# mcu.net
KiCad netlist of a schematic drawn in Altium Designer
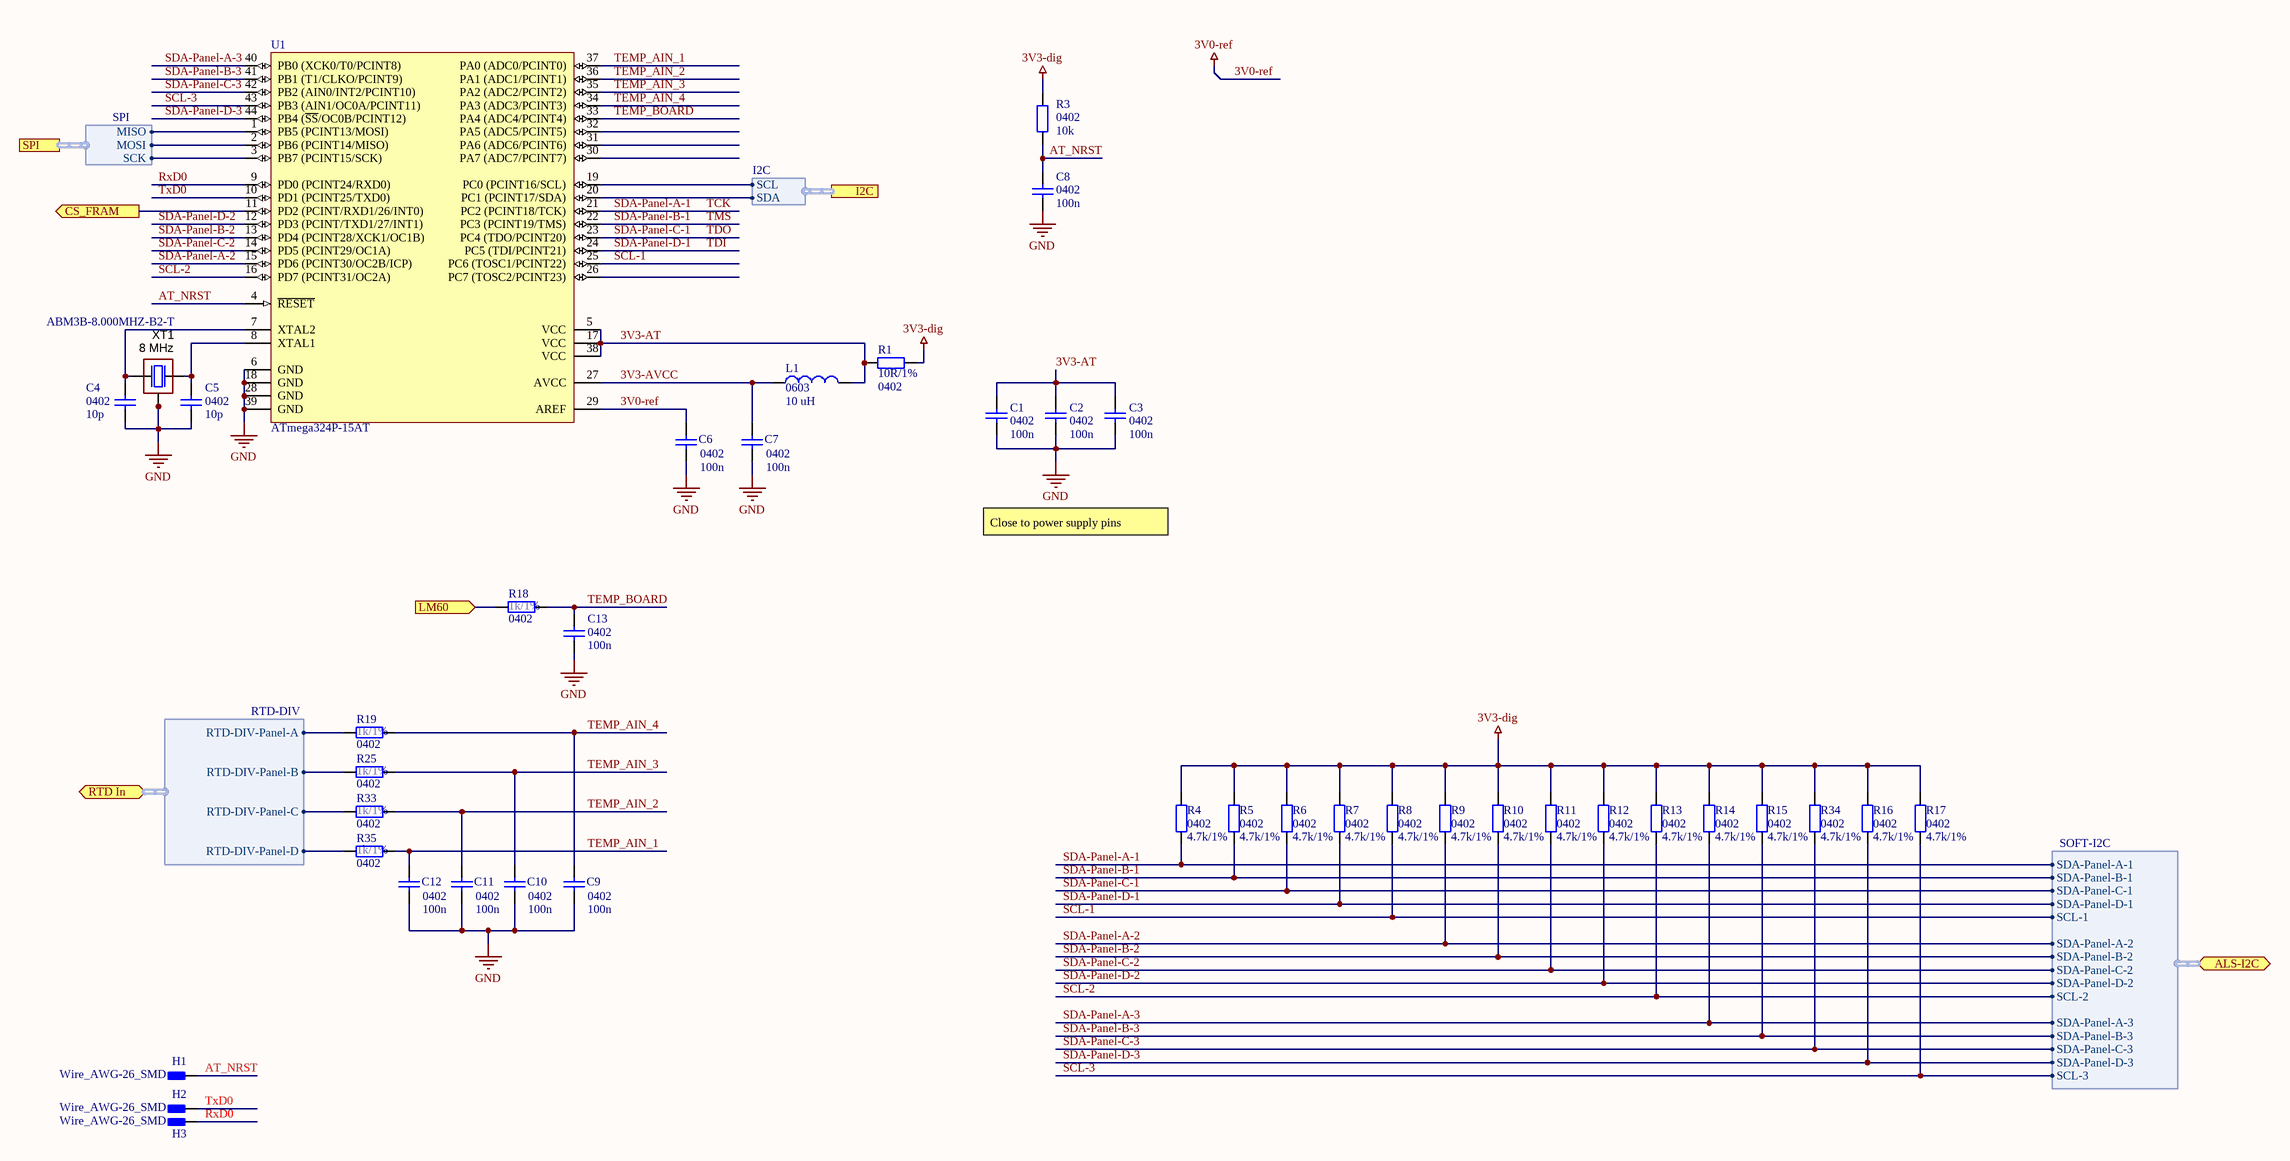
[diagram p0: mcu.SchDoc]

(export (version "E")
  (design (tool "Eeschema 10.0.6"))
  (components
    (comp (ref "C1")
      (value "0402")
      (footprint "SMD_Capacitor_0402")
      (description "Capacitor")
      (fields (field (name "ALTIUM_VALUE") "100n") (field (name "PUBLISHER") "Altium Limited"))
      (libsource (lib "Miscellaneous Devices") (part "Cap"))
    )
    (comp (ref "C2")
      (value "0402")
      (footprint "SMD_Capacitor_0402")
      (description "Capacitor")
      (fields (field (name "ALTIUM_VALUE") "100n") (field (name "PUBLISHER") "Altium Limited"))
      (libsource (lib "Miscellaneous Devices") (part "Cap"))
    )
    (comp (ref "C3")
      (value "0402")
      (footprint "SMD_Capacitor_0402")
      (description "Capacitor")
      (fields (field (name "ALTIUM_VALUE") "100n") (field (name "PUBLISHER") "Altium Limited"))
      (libsource (lib "Miscellaneous Devices") (part "Cap"))
    )
    (comp (ref "C4")
      (value "0402")
      (footprint "SMD_Capacitor_0402")
      (description "Capacitor")
      (fields (field (name "ALTIUM_VALUE") "10p") (field (name "PUBLISHER") "Altium Limited"))
      (libsource (lib "Miscellaneous Devices") (part "Cap"))
    )
    (comp (ref "C5")
      (value "0402")
      (footprint "SMD_Capacitor_0402")
      (description "Capacitor")
      (fields (field (name "ALTIUM_VALUE") "10p") (field (name "PUBLISHER") "Altium Limited"))
      (libsource (lib "Miscellaneous Devices") (part "Cap"))
    )
    (comp (ref "C6")
      (value "0402")
      (footprint "SMD_Capacitor_0402")
      (description "Capacitor")
      (fields (field (name "ALTIUM_VALUE") "100n") (field (name "PUBLISHER") "Altium Limited"))
      (libsource (lib "Miscellaneous Devices") (part "Cap"))
    )
    (comp (ref "C7")
      (value "0402")
      (footprint "SMD_Capacitor_0402")
      (description "Capacitor")
      (fields (field (name "ALTIUM_VALUE") "100n") (field (name "PUBLISHER") "Altium Limited"))
      (libsource (lib "Miscellaneous Devices") (part "Cap"))
    )
    (comp (ref "C8")
      (value "0402")
      (footprint "SMD_Capacitor_0402")
      (description "Capacitor")
      (fields (field (name "ALTIUM_VALUE") "100n") (field (name "PUBLISHER") "Altium Limited"))
      (libsource (lib "Miscellaneous Devices") (part "Cap"))
    )
    (comp (ref "C9")
      (value "0402")
      (footprint "SMD_Capacitor_0402")
      (description "Capacitor")
      (fields (field (name "ALTIUM_VALUE") "100n") (field (name "PUBLISHER") "Altium Limited"))
      (libsource (lib "Miscellaneous Devices") (part "Cap"))
    )
    (comp (ref "C10")
      (value "0402")
      (footprint "SMD_Capacitor_0402")
      (description "Capacitor")
      (fields (field (name "ALTIUM_VALUE") "100n") (field (name "PUBLISHER") "Altium Limited"))
      (libsource (lib "Miscellaneous Devices") (part "Cap"))
    )
    (comp (ref "C11")
      (value "0402")
      (footprint "SMD_Capacitor_0402")
      (description "Capacitor")
      (fields (field (name "ALTIUM_VALUE") "100n") (field (name "PUBLISHER") "Altium Limited"))
      (libsource (lib "Miscellaneous Devices") (part "Cap"))
    )
    (comp (ref "C12")
      (value "0402")
      (footprint "SMD_Capacitor_0402")
      (description "Capacitor")
      (fields (field (name "ALTIUM_VALUE") "100n") (field (name "PUBLISHER") "Altium Limited"))
      (libsource (lib "Miscellaneous Devices") (part "Cap"))
    )
    (comp (ref "C13")
      (value "0402")
      (footprint "SMD_Capacitor_0402")
      (description "Capacitor")
      (fields (field (name "ALTIUM_VALUE") "100n") (field (name "PUBLISHER") "Altium Limited"))
      (libsource (lib "Miscellaneous Devices") (part "Cap"))
    )
    (comp (ref "H1")
      (value "Wire_AWG-26_SMD")
      (footprint "Wire_AWG-26_SMD")
      (description "SMD wire solder point.")
      (libsource (lib "connectors_printed-circuit-board") (part "Wire_AWG-26_SMD"))
    )
    (comp (ref "H2")
      (value "Wire_AWG-26_SMD")
      (footprint "Wire_AWG-26_SMD")
      (description "SMD wire solder point.")
      (libsource (lib "connectors_printed-circuit-board") (part "Wire_AWG-26_SMD"))
    )
    (comp (ref "H3")
      (value "Wire_AWG-26_SMD")
      (footprint "Wire_AWG-26_SMD")
      (description "SMD wire solder point.")
      (libsource (lib "connectors_printed-circuit-board") (part "Wire_AWG-26_SMD"))
    )
    (comp (ref "L1")
      (value "10 uH")
      (footprint "SMD_Resistor_0603")
      (description "Inductor")
      (fields (field (name "PACKAGEREFERENCE") "0603") (field (name "PUBLISHER") "Altium Limited"))
      (libsource (lib "Miscellaneous Devices") (part "Inductor"))
    )
    (comp (ref "R1")
      (value "10R/1%")
      (footprint "SMD_Resistor_0402")
      (description "10R/1% Vishay CRCW 0402 Resistor. 63mW, 100ppm, 50V.")
      (fields
        (field (name "MANUFACTURER") "Vishay")
        (field (name "MANUFACTURERPARTNUMBER") "CRCW040210R0FKxxxx")
        (field (name "PACKAGE") "0402")
      )
      (libsource (lib "resistors") (part "CRCW040210R0FKxxxx"))
    )
    (comp (ref "R3")
      (value "0402")
      (footprint "SMD_Capacitor_0402")
      (description "Resistor")
      (fields (field (name "ALTIUM_VALUE") "10k") (field (name "PUBLISHER") "Altium Limited"))
      (libsource (lib "Miscellaneous Devices") (part "Res2"))
    )
    (comp (ref "R4")
      (value "4.7k/1%")
      (footprint "SMD_Resistor_0402")
      (description "4.7k/1% Vishay CRCW 0402 Resistor. 63mW, 100ppm, 50V.")
      (fields
        (field (name "MANUFACTURERPARTNUMBER") "CRCW04024K70FKxxxx")
        (field (name "MANUFACTURER") "Vishay")
        (field (name "PACKAGE") "0402")
      )
      (libsource (lib "resistors") (part "CRCW04024K70FKxxxx"))
    )
    (comp (ref "R5")
      (value "4.7k/1%")
      (footprint "SMD_Resistor_0402")
      (description "4.7k/1% Vishay CRCW 0402 Resistor. 63mW, 100ppm, 50V.")
      (fields
        (field (name "MANUFACTURERPARTNUMBER") "CRCW04024K70FKxxxx")
        (field (name "MANUFACTURER") "Vishay")
        (field (name "PACKAGE") "0402")
      )
      (libsource (lib "resistors") (part "CRCW04024K70FKxxxx"))
    )
    (comp (ref "R6")
      (value "4.7k/1%")
      (footprint "SMD_Resistor_0402")
      (description "4.7k/1% Vishay CRCW 0402 Resistor. 63mW, 100ppm, 50V.")
      (fields
        (field (name "MANUFACTURERPARTNUMBER") "CRCW04024K70FKxxxx")
        (field (name "MANUFACTURER") "Vishay")
        (field (name "PACKAGE") "0402")
      )
      (libsource (lib "resistors") (part "CRCW04024K70FKxxxx"))
    )
    (comp (ref "R7")
      (value "4.7k/1%")
      (footprint "SMD_Resistor_0402")
      (description "4.7k/1% Vishay CRCW 0402 Resistor. 63mW, 100ppm, 50V.")
      (fields
        (field (name "MANUFACTURERPARTNUMBER") "CRCW04024K70FKxxxx")
        (field (name "MANUFACTURER") "Vishay")
        (field (name "PACKAGE") "0402")
      )
      (libsource (lib "resistors") (part "CRCW04024K70FKxxxx"))
    )
    (comp (ref "R8")
      (value "4.7k/1%")
      (footprint "SMD_Resistor_0402")
      (description "4.7k/1% Vishay CRCW 0402 Resistor. 63mW, 100ppm, 50V.")
      (fields
        (field (name "MANUFACTURERPARTNUMBER") "CRCW04024K70FKxxxx")
        (field (name "MANUFACTURER") "Vishay")
        (field (name "PACKAGE") "0402")
      )
      (libsource (lib "resistors") (part "CRCW04024K70FKxxxx"))
    )
    (comp (ref "R9")
      (value "4.7k/1%")
      (footprint "SMD_Resistor_0402")
      (description "4.7k/1% Vishay CRCW 0402 Resistor. 63mW, 100ppm, 50V.")
      (fields
        (field (name "MANUFACTURERPARTNUMBER") "CRCW04024K70FKxxxx")
        (field (name "MANUFACTURER") "Vishay")
        (field (name "PACKAGE") "0402")
      )
      (libsource (lib "resistors") (part "CRCW04024K70FKxxxx"))
    )
    (comp (ref "R10")
      (value "4.7k/1%")
      (footprint "SMD_Resistor_0402")
      (description "4.7k/1% Vishay CRCW 0402 Resistor. 63mW, 100ppm, 50V.")
      (fields
        (field (name "MANUFACTURERPARTNUMBER") "CRCW04024K70FKxxxx")
        (field (name "MANUFACTURER") "Vishay")
        (field (name "PACKAGE") "0402")
      )
      (libsource (lib "resistors") (part "CRCW04024K70FKxxxx"))
    )
    (comp (ref "R11")
      (value "4.7k/1%")
      (footprint "SMD_Resistor_0402")
      (description "4.7k/1% Vishay CRCW 0402 Resistor. 63mW, 100ppm, 50V.")
      (fields
        (field (name "MANUFACTURERPARTNUMBER") "CRCW04024K70FKxxxx")
        (field (name "MANUFACTURER") "Vishay")
        (field (name "PACKAGE") "0402")
      )
      (libsource (lib "resistors") (part "CRCW04024K70FKxxxx"))
    )
    (comp (ref "R12")
      (value "4.7k/1%")
      (footprint "SMD_Resistor_0402")
      (description "4.7k/1% Vishay CRCW 0402 Resistor. 63mW, 100ppm, 50V.")
      (fields
        (field (name "MANUFACTURERPARTNUMBER") "CRCW04024K70FKxxxx")
        (field (name "MANUFACTURER") "Vishay")
        (field (name "PACKAGE") "0402")
      )
      (libsource (lib "resistors") (part "CRCW04024K70FKxxxx"))
    )
    (comp (ref "R13")
      (value "4.7k/1%")
      (footprint "SMD_Resistor_0402")
      (description "4.7k/1% Vishay CRCW 0402 Resistor. 63mW, 100ppm, 50V.")
      (fields
        (field (name "MANUFACTURERPARTNUMBER") "CRCW04024K70FKxxxx")
        (field (name "MANUFACTURER") "Vishay")
        (field (name "PACKAGE") "0402")
      )
      (libsource (lib "resistors") (part "CRCW04024K70FKxxxx"))
    )
    (comp (ref "R14")
      (value "4.7k/1%")
      (footprint "SMD_Resistor_0402")
      (description "4.7k/1% Vishay CRCW 0402 Resistor. 63mW, 100ppm, 50V.")
      (fields
        (field (name "MANUFACTURERPARTNUMBER") "CRCW04024K70FKxxxx")
        (field (name "MANUFACTURER") "Vishay")
        (field (name "PACKAGE") "0402")
      )
      (libsource (lib "resistors") (part "CRCW04024K70FKxxxx"))
    )
    (comp (ref "R15")
      (value "4.7k/1%")
      (footprint "SMD_Resistor_0402")
      (description "4.7k/1% Vishay CRCW 0402 Resistor. 63mW, 100ppm, 50V.")
      (fields
        (field (name "MANUFACTURERPARTNUMBER") "CRCW04024K70FKxxxx")
        (field (name "MANUFACTURER") "Vishay")
        (field (name "PACKAGE") "0402")
      )
      (libsource (lib "resistors") (part "CRCW04024K70FKxxxx"))
    )
    (comp (ref "R16")
      (value "4.7k/1%")
      (footprint "SMD_Resistor_0402")
      (description "4.7k/1% Vishay CRCW 0402 Resistor. 63mW, 100ppm, 50V.")
      (fields
        (field (name "MANUFACTURERPARTNUMBER") "CRCW04024K70FKxxxx")
        (field (name "MANUFACTURER") "Vishay")
        (field (name "PACKAGE") "0402")
      )
      (libsource (lib "resistors") (part "CRCW04024K70FKxxxx"))
    )
    (comp (ref "R17")
      (value "4.7k/1%")
      (footprint "SMD_Resistor_0402")
      (description "4.7k/1% Vishay CRCW 0402 Resistor. 63mW, 100ppm, 50V.")
      (fields
        (field (name "MANUFACTURERPARTNUMBER") "CRCW04024K70FKxxxx")
        (field (name "MANUFACTURER") "Vishay")
        (field (name "PACKAGE") "0402")
      )
      (libsource (lib "resistors") (part "CRCW04024K70FKxxxx"))
    )
    (comp (ref "R18")
      (value "1k/1%")
      (footprint "SMD_Resistor_0402")
      (description "1k/1% Vishay CRCW 0402 Resistor. 63mW, 100ppm, 50V.")
      (fields
        (field (name "MANUFACTURER") "Vishay")
        (field (name "MANUFACTURERPARTNUMBER") "CRCW04021K00FKxxxx")
        (field (name "PACKAGE") "0402")
      )
      (libsource (lib "resistors") (part "CRCW04021K00FKxxxx"))
    )
    (comp (ref "R19")
      (value "1k/1%")
      (footprint "SMD_Resistor_0402")
      (description "1k/1% Vishay CRCW 0402 Resistor. 63mW, 100ppm, 50V.")
      (fields
        (field (name "MANUFACTURER") "Vishay")
        (field (name "MANUFACTURERPARTNUMBER") "CRCW04021K00FKxxxx")
        (field (name "PACKAGE") "0402")
      )
      (libsource (lib "resistors") (part "CRCW04021K00FKxxxx"))
    )
    (comp (ref "R25")
      (value "1k/1%")
      (footprint "SMD_Resistor_0402")
      (description "1k/1% Vishay CRCW 0402 Resistor. 63mW, 100ppm, 50V.")
      (fields
        (field (name "MANUFACTURER") "Vishay")
        (field (name "MANUFACTURERPARTNUMBER") "CRCW04021K00FKxxxx")
        (field (name "PACKAGE") "0402")
      )
      (libsource (lib "resistors") (part "CRCW04021K00FKxxxx"))
    )
    (comp (ref "R33")
      (value "1k/1%")
      (footprint "SMD_Resistor_0402")
      (description "1k/1% Vishay CRCW 0402 Resistor. 63mW, 100ppm, 50V.")
      (fields
        (field (name "MANUFACTURER") "Vishay")
        (field (name "MANUFACTURERPARTNUMBER") "CRCW04021K00FKxxxx")
        (field (name "PACKAGE") "0402")
      )
      (libsource (lib "resistors") (part "CRCW04021K00FKxxxx"))
    )
    (comp (ref "R34")
      (value "4.7k/1%")
      (footprint "SMD_Resistor_0402")
      (description "4.7k/1% Vishay CRCW 0402 Resistor. 63mW, 100ppm, 50V.")
      (fields
        (field (name "MANUFACTURERPARTNUMBER") "CRCW04024K70FKxxxx")
        (field (name "MANUFACTURER") "Vishay")
        (field (name "PACKAGE") "0402")
      )
      (libsource (lib "resistors") (part "CRCW04024K70FKxxxx"))
    )
    (comp (ref "R35")
      (value "1k/1%")
      (footprint "SMD_Resistor_0402")
      (description "1k/1% Vishay CRCW 0402 Resistor. 63mW, 100ppm, 50V.")
      (fields
        (field (name "MANUFACTURER") "Vishay")
        (field (name "MANUFACTURERPARTNUMBER") "CRCW04021K00FKxxxx")
        (field (name "PACKAGE") "0402")
      )
      (libsource (lib "resistors") (part "CRCW04021K00FKxxxx"))
    )
    (comp (ref "U1")
      (value "ATmega324P-15AT")
      (footprint "44ML_N")
      (libsource (lib "Atmel Microcontroller AVR Automotive") (part "ATmega324P-15AT"))
    )
    (comp (ref "XT1")
      (value "8 MHz")
      (footprint "SMD, 5mm x 3.2mm")
      (description "Resonator Ceramic")
      (fields (field (name "MANUFACTURER PART NUMBER") "ABM3B-8.000MHZ-B2-T"))
      (libsource (lib "crystal") (part "ABM3B-8.000MHZ-B2-T"))
    )
  )
  (nets
    (net (code "5") (name "/3V3-AT") (class "Default")
      (node (ref "C1") (pin "2") (pinfunction "2_2") (pintype "passive"))
      (node (ref "C2") (pin "2") (pinfunction "2_2") (pintype "passive"))
      (node (ref "C3") (pin "2") (pinfunction "2_2") (pintype "passive"))
      (node (ref "L1") (pin "2") (pinfunction "2_2") (pintype "passive"))
      (node (ref "R1") (pin "2") (pinfunction "2_2") (pintype "passive"))
      (node (ref "U1") (pin "17") (pinfunction "VCC_17") (pintype "power_in"))
      (node (ref "U1") (pin "38") (pinfunction "VCC_38") (pintype "power_in"))
      (node (ref "U1") (pin "5") (pinfunction "VCC_5") (pintype "power_in"))
    )
    (net (code "6") (name "/3V3-AVCC") (class "Default")
      (node (ref "C7") (pin "2") (pinfunction "2_2") (pintype "passive"))
      (node (ref "L1") (pin "1") (pinfunction "1_1") (pintype "passive"))
      (node (ref "U1") (pin "27") (pinfunction "AVCC_27") (pintype "power_in"))
    )
    (net (code "7") (name "/AT_NRST") (class "Default")
      (node (ref "C8") (pin "2") (pinfunction "2_2") (pintype "passive"))
      (node (ref "H1") (pin "1") (pinfunction "1_1") (pintype "passive"))
      (node (ref "R3") (pin "1") (pinfunction "1_1") (pintype "passive"))
      (node (ref "U1") (pin "4") (pinfunction "~{RESET}_4") (pintype "input"))
    )
    (net (code "8") (name "/CS_FRAM") (class "Default")
      (node (ref "U1") (pin "11") (pinfunction "PD2_(PCINT/RXD1/26/INT0)_11") (pintype "bidirectional"))
    )
    (net (code "9") (name "/LM60") (class "Default")
      (node (ref "R18") (pin "1") (pinfunction "1_1") (pintype "passive"))
    )
    (net (code "10") (name "/MISO") (class "Default")
      (node (ref "U1") (pin "1") (pinfunction "PB5_(PCINT13/MOSI)_1") (pintype "bidirectional"))
    )
    (net (code "11") (name "/MOSI") (class "Default")
      (node (ref "U1") (pin "2") (pinfunction "PB6_(PCINT14/MISO)_2") (pintype "bidirectional"))
    )
    (net (code "12") (name "/RTD-DIV-Panel-A") (class "Default")
      (node (ref "R19") (pin "1") (pinfunction "1_1") (pintype "passive"))
    )
    (net (code "13") (name "/RTD-DIV-Panel-B") (class "Default")
      (node (ref "R25") (pin "1") (pinfunction "1_1") (pintype "passive"))
    )
    (net (code "14") (name "/RTD-DIV-Panel-C") (class "Default")
      (node (ref "R33") (pin "1") (pinfunction "1_1") (pintype "passive"))
    )
    (net (code "15") (name "/RTD-DIV-Panel-D") (class "Default")
      (node (ref "R35") (pin "1") (pinfunction "1_1") (pintype "passive"))
    )
    (net (code "16") (name "/RxD0") (class "Default")
      (node (ref "H3") (pin "1") (pinfunction "1_1") (pintype "passive"))
      (node (ref "U1") (pin "9") (pinfunction "PD0_(PCINT24/RXD0)_9") (pintype "bidirectional"))
    )
    (net (code "17") (name "/SCK") (class "Default")
      (node (ref "U1") (pin "3") (pinfunction "PB7_(PCINT15/SCK)_3") (pintype "bidirectional"))
    )
    (net (code "18") (name "/SCL") (class "Default")
      (node (ref "U1") (pin "19") (pinfunction "PC0_(PCINT16/SCL)_19") (pintype "bidirectional"))
    )
    (net (code "19") (name "/SCL-1") (class "Default")
      (node (ref "R8") (pin "2") (pinfunction "2_2") (pintype "passive"))
      (node (ref "U1") (pin "25") (pinfunction "PC6_(TOSC1/PCINT22)_25") (pintype "bidirectional"))
    )
    (net (code "20") (name "/SCL-2") (class "Default")
      (node (ref "R13") (pin "2") (pinfunction "2_2") (pintype "passive"))
      (node (ref "U1") (pin "16") (pinfunction "PD7_(PCINT31/OC2A)_16") (pintype "bidirectional"))
    )
    (net (code "21") (name "/SCL-3") (class "Default")
      (node (ref "R17") (pin "2") (pinfunction "2_2") (pintype "passive"))
      (node (ref "U1") (pin "43") (pinfunction "PB3_(AIN1/OC0A/PCINT11)_43") (pintype "bidirectional"))
    )
    (net (code "22") (name "/SDA") (class "Default")
      (node (ref "U1") (pin "20") (pinfunction "PC1_(PCINT17/SDA)_20") (pintype "bidirectional"))
    )
    (net (code "23") (name "/SDA-Panel-A-1") (class "Default")
      (node (ref "R4") (pin "2") (pinfunction "2_2") (pintype "passive"))
      (node (ref "U1") (pin "21") (pinfunction "PC2_(PCINT18/TCK)_21") (pintype "bidirectional"))
    )
    (net (code "24") (name "/SDA-Panel-A-2") (class "Default")
      (node (ref "R9") (pin "2") (pinfunction "2_2") (pintype "passive"))
      (node (ref "U1") (pin "15") (pinfunction "PD6_(PCINT30/OC2B/ICP)_15") (pintype "bidirectional"))
    )
    (net (code "25") (name "/SDA-Panel-A-3") (class "Default")
      (node (ref "R14") (pin "2") (pinfunction "2_2") (pintype "passive"))
      (node (ref "U1") (pin "40") (pinfunction "PB0_(XCK0/T0/PCINT8)_40") (pintype "bidirectional"))
    )
    (net (code "26") (name "/SDA-Panel-B-1") (class "Default")
      (node (ref "R5") (pin "2") (pinfunction "2_2") (pintype "passive"))
      (node (ref "U1") (pin "22") (pinfunction "PC3_(PCINT19/TMS)_22") (pintype "bidirectional"))
    )
    (net (code "27") (name "/SDA-Panel-B-2") (class "Default")
      (node (ref "R10") (pin "2") (pinfunction "2_2") (pintype "passive"))
      (node (ref "U1") (pin "13") (pinfunction "PD4_(PCINT28/XCK1/OC1B)_13") (pintype "bidirectional"))
    )
    (net (code "28") (name "/SDA-Panel-B-3") (class "Default")
      (node (ref "R15") (pin "2") (pinfunction "2_2") (pintype "passive"))
      (node (ref "U1") (pin "41") (pinfunction "PB1_(T1/CLKO/PCINT9)_41") (pintype "bidirectional"))
    )
    (net (code "29") (name "/SDA-Panel-C-1") (class "Default")
      (node (ref "R6") (pin "2") (pinfunction "2_2") (pintype "passive"))
      (node (ref "U1") (pin "23") (pinfunction "PC4_(TDO/PCINT20)_23") (pintype "bidirectional"))
    )
    (net (code "30") (name "/SDA-Panel-C-2") (class "Default")
      (node (ref "R11") (pin "2") (pinfunction "2_2") (pintype "passive"))
      (node (ref "U1") (pin "14") (pinfunction "PD5_(PCINT29/OC1A)_14") (pintype "bidirectional"))
    )
    (net (code "31") (name "/SDA-Panel-C-3") (class "Default")
      (node (ref "R34") (pin "2") (pinfunction "2_2") (pintype "passive"))
      (node (ref "U1") (pin "42") (pinfunction "PB2_(AIN0/INT2/PCINT10)_42") (pintype "bidirectional"))
    )
    (net (code "32") (name "/SDA-Panel-D-1") (class "Default")
      (node (ref "R7") (pin "2") (pinfunction "2_2") (pintype "passive"))
      (node (ref "U1") (pin "24") (pinfunction "PC5_(TDI/PCINT21)_24") (pintype "bidirectional"))
    )
    (net (code "33") (name "/SDA-Panel-D-2") (class "Default")
      (node (ref "R12") (pin "2") (pinfunction "2_2") (pintype "passive"))
      (node (ref "U1") (pin "12") (pinfunction "PD3_(PCINT/TXD1/27/INT1)_12") (pintype "bidirectional"))
    )
    (net (code "34") (name "/SDA-Panel-D-3") (class "Default")
      (node (ref "R16") (pin "2") (pinfunction "2_2") (pintype "passive"))
      (node (ref "U1") (pin "44") (pinfunction "PB4_(~{SS}/OC0B/PCINT12)_44") (pintype "bidirectional"))
    )
    (net (code "35") (name "/TEMP_AIN_1") (class "Default")
      (node (ref "C12") (pin "2") (pinfunction "2_2") (pintype "passive"))
      (node (ref "R35") (pin "2") (pinfunction "2_2") (pintype "passive"))
      (node (ref "U1") (pin "37") (pinfunction "PA0_(ADC0/PCINT0)_37") (pintype "bidirectional"))
    )
    (net (code "36") (name "/TEMP_AIN_2") (class "Default")
      (node (ref "C11") (pin "2") (pinfunction "2_2") (pintype "passive"))
      (node (ref "R33") (pin "2") (pinfunction "2_2") (pintype "passive"))
      (node (ref "U1") (pin "36") (pinfunction "PA1_(ADC1/PCINT1)_36") (pintype "bidirectional"))
    )
    (net (code "37") (name "/TEMP_AIN_3") (class "Default")
      (node (ref "C10") (pin "2") (pinfunction "2_2") (pintype "passive"))
      (node (ref "R25") (pin "2") (pinfunction "2_2") (pintype "passive"))
      (node (ref "U1") (pin "35") (pinfunction "PA2_(ADC2/PCINT2)_35") (pintype "bidirectional"))
    )
    (net (code "38") (name "/TEMP_AIN_4") (class "Default")
      (node (ref "C9") (pin "2") (pinfunction "2_2") (pintype "passive"))
      (node (ref "R19") (pin "2") (pinfunction "2_2") (pintype "passive"))
      (node (ref "U1") (pin "34") (pinfunction "PA3_(ADC3/PCINT3)_34") (pintype "bidirectional"))
    )
    (net (code "39") (name "/TEMP_BOARD") (class "Default")
      (node (ref "C13") (pin "2") (pinfunction "2_2") (pintype "passive"))
      (node (ref "R18") (pin "2") (pinfunction "2_2") (pintype "passive"))
      (node (ref "U1") (pin "33") (pinfunction "PA4_(ADC4/PCINT4)_33") (pintype "bidirectional"))
    )
    (net (code "40") (name "/TxD0") (class "Default")
      (node (ref "H2") (pin "1") (pinfunction "1_1") (pintype "passive"))
      (node (ref "U1") (pin "10") (pinfunction "PD1_(PCINT25/TXD0)_10") (pintype "bidirectional"))
    )
    (net (code "45") (name "3V0-ref") (class "Default")
      (node (ref "C6") (pin "2") (pinfunction "2_2") (pintype "passive"))
      (node (ref "U1") (pin "29") (pinfunction "AREF_29") (pintype "power_in"))
    )
    (net (code "46") (name "3V3-dig") (class "Default")
      (node (ref "R1") (pin "1") (pinfunction "1_1") (pintype "passive"))
      (node (ref "R10") (pin "1") (pinfunction "1_1") (pintype "passive"))
      (node (ref "R11") (pin "1") (pinfunction "1_1") (pintype "passive"))
      (node (ref "R12") (pin "1") (pinfunction "1_1") (pintype "passive"))
      (node (ref "R13") (pin "1") (pinfunction "1_1") (pintype "passive"))
      (node (ref "R14") (pin "1") (pinfunction "1_1") (pintype "passive"))
      (node (ref "R15") (pin "1") (pinfunction "1_1") (pintype "passive"))
      (node (ref "R16") (pin "1") (pinfunction "1_1") (pintype "passive"))
      (node (ref "R17") (pin "1") (pinfunction "1_1") (pintype "passive"))
      (node (ref "R3") (pin "2") (pinfunction "2_2") (pintype "passive"))
      (node (ref "R34") (pin "1") (pinfunction "1_1") (pintype "passive"))
      (node (ref "R4") (pin "1") (pinfunction "1_1") (pintype "passive"))
      (node (ref "R5") (pin "1") (pinfunction "1_1") (pintype "passive"))
      (node (ref "R6") (pin "1") (pinfunction "1_1") (pintype "passive"))
      (node (ref "R7") (pin "1") (pinfunction "1_1") (pintype "passive"))
      (node (ref "R8") (pin "1") (pinfunction "1_1") (pintype "passive"))
      (node (ref "R9") (pin "1") (pinfunction "1_1") (pintype "passive"))
    )
    (net (code "47") (name "GND") (class "Default")
      (node (ref "C1") (pin "1") (pinfunction "1_1") (pintype "passive"))
      (node (ref "C10") (pin "1") (pinfunction "1_1") (pintype "passive"))
      (node (ref "C11") (pin "1") (pinfunction "1_1") (pintype "passive"))
      (node (ref "C12") (pin "1") (pinfunction "1_1") (pintype "passive"))
      (node (ref "C13") (pin "1") (pinfunction "1_1") (pintype "passive"))
      (node (ref "C2") (pin "1") (pinfunction "1_1") (pintype "passive"))
      (node (ref "C3") (pin "1") (pinfunction "1_1") (pintype "passive"))
      (node (ref "C4") (pin "1") (pinfunction "1_1") (pintype "passive"))
      (node (ref "C5") (pin "1") (pinfunction "1_1") (pintype "passive"))
      (node (ref "C6") (pin "1") (pinfunction "1_1") (pintype "passive"))
      (node (ref "C7") (pin "1") (pinfunction "1_1") (pintype "passive"))
      (node (ref "C8") (pin "1") (pinfunction "1_1") (pintype "passive"))
      (node (ref "C9") (pin "1") (pinfunction "1_1") (pintype "passive"))
      (node (ref "U1") (pin "18") (pinfunction "GND_18") (pintype "power_in"))
      (node (ref "U1") (pin "28") (pinfunction "GND_28") (pintype "power_in"))
      (node (ref "U1") (pin "39") (pinfunction "GND_39") (pintype "power_in"))
      (node (ref "U1") (pin "6") (pinfunction "GND_6") (pintype "power_in"))
      (node (ref "XT1") (pin "3") (pinfunction "GND_3") (pintype "passive"))
      (node (ref "XT1") (pin "4") (pinfunction "GND_4") (pintype "passive"))
    )
    (net (code "48") (name "Net-(U1-XTAL1)") (class "Default")
      (node (ref "C5") (pin "2") (pinfunction "2_2") (pintype "passive"))
      (node (ref "U1") (pin "8") (pinfunction "XTAL1_8") (pintype "passive"))
      (node (ref "XT1") (pin "2") (pinfunction "out_2") (pintype "passive"))
    )
    (net (code "49") (name "Net-(U1-XTAL2)") (class "Default")
      (node (ref "C4") (pin "2") (pinfunction "2_2") (pintype "passive"))
      (node (ref "U1") (pin "7") (pinfunction "XTAL2_7") (pintype "passive"))
      (node (ref "XT1") (pin "1") (pinfunction "inp_1") (pintype "passive"))
    )
    (net (code "50") (name "unconnected-(U1-PA5_(ADC5{slash}PCINT5)-Pad32)") (class "Default")
      (node (ref "U1") (pin "32") (pinfunction "PA5_(ADC5/PCINT5)_32") (pintype "bidirectional"))
    )
    (net (code "51") (name "unconnected-(U1-PA6_(ADC6{slash}PCINT6)-Pad31)") (class "Default")
      (node (ref "U1") (pin "31") (pinfunction "PA6_(ADC6/PCINT6)_31") (pintype "bidirectional"))
    )
    (net (code "52") (name "unconnected-(U1-PA7_(ADC7{slash}PCINT7)-Pad30)") (class "Default")
      (node (ref "U1") (pin "30") (pinfunction "PA7_(ADC7/PCINT7)_30") (pintype "bidirectional"))
    )
    (net (code "53") (name "unconnected-(U1-PC7_(TOSC2{slash}PCINT23)-Pad26)") (class "Default")
      (node (ref "U1") (pin "26") (pinfunction "PC7_(TOSC2/PCINT23)_26") (pintype "bidirectional"))
    )
  )
)
